# blink1mk2_v2d.net
KiCad netlist of a schematic drawn in EAGLE
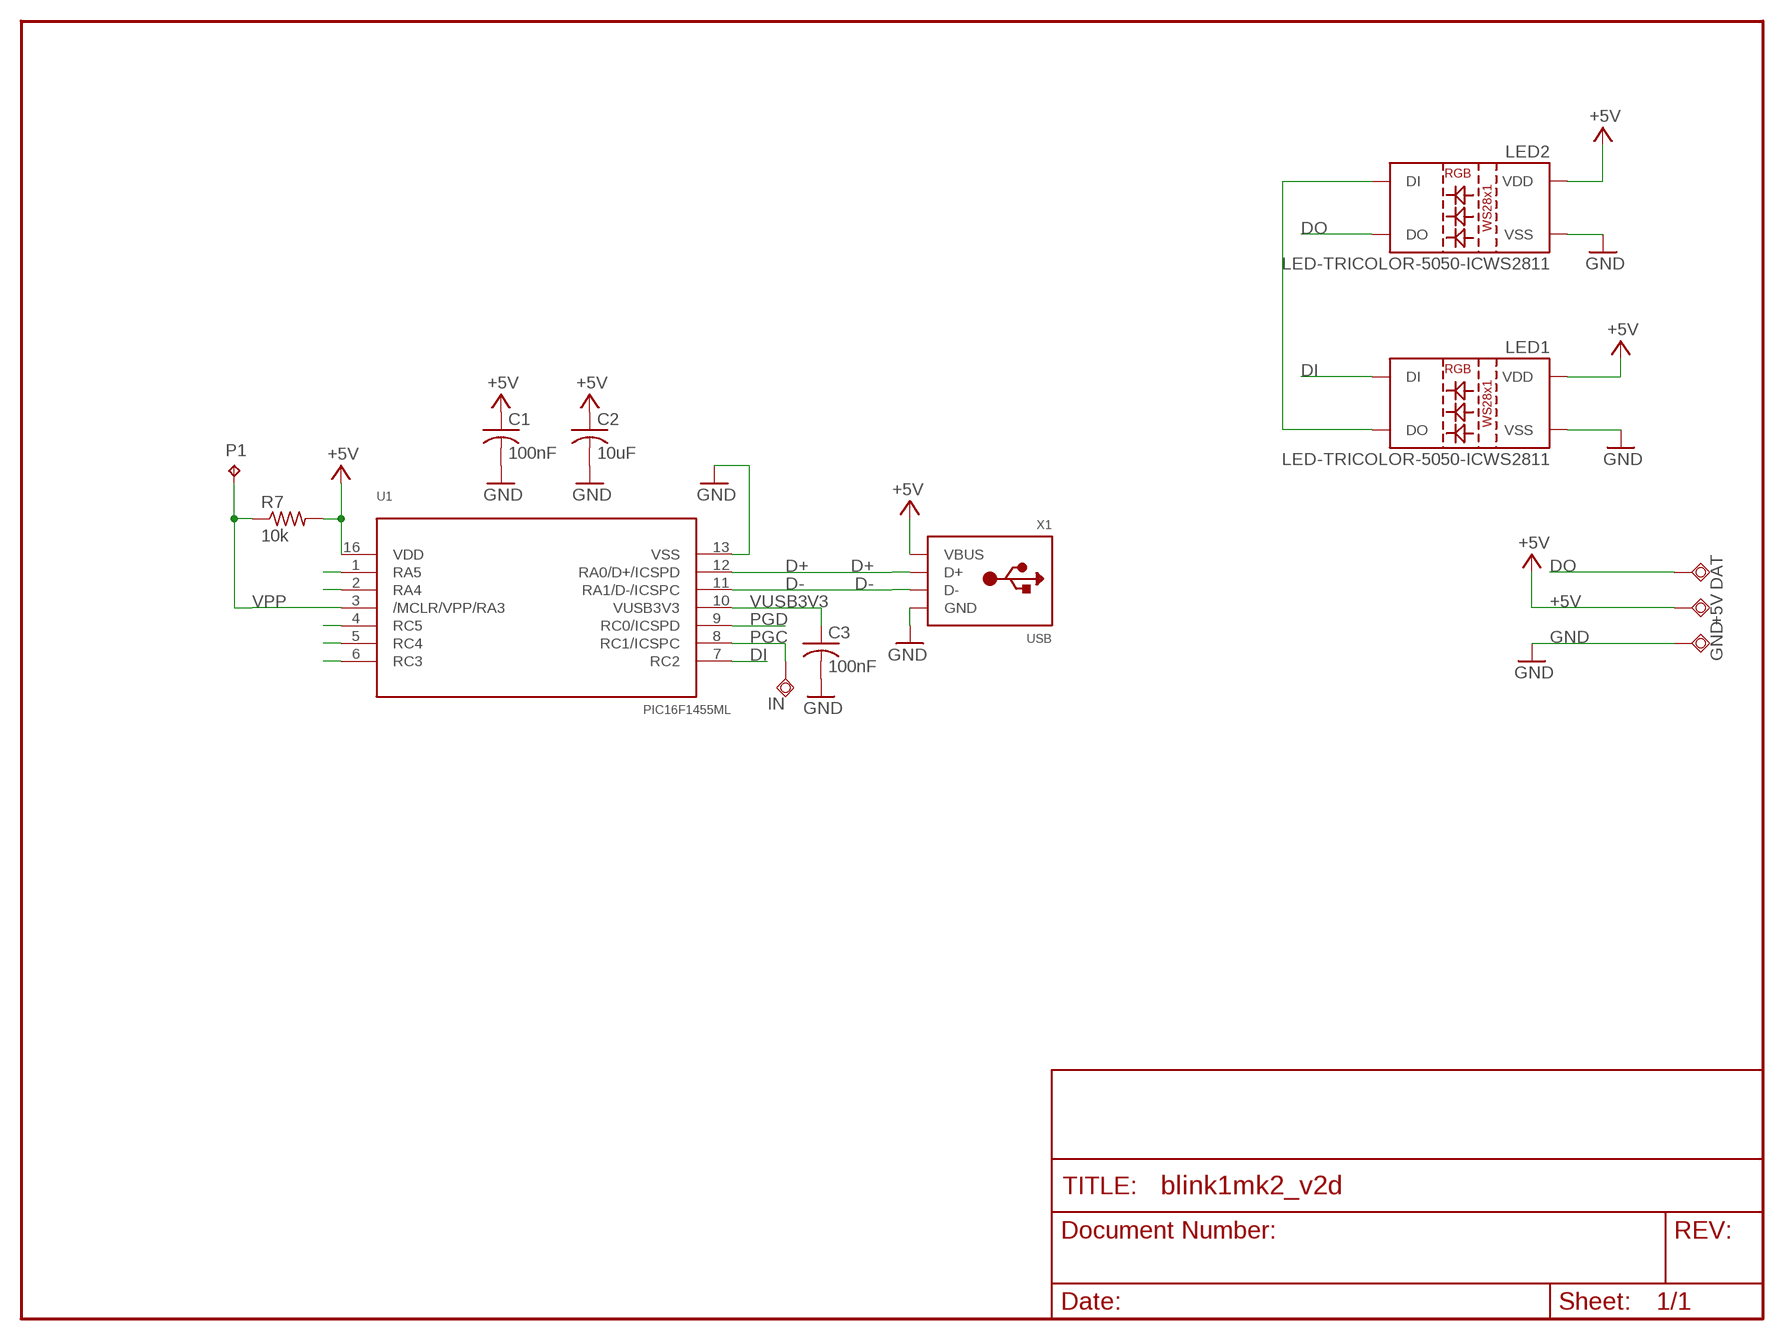
[diagram p0: schematic, sheet 1]

(export (version "E")
  (design (tool "Eeschema 10.0.6"))
  (components
    (comp (ref "+5V")
      (value "TPSQTP12SQ")
      (footprint "eagle-import:TP12SQ")
      (libsource (lib "eagle-import") (part "TPSQTP12SQ"))
    )
    (comp (ref "C1")
      (value "100nF")
      (footprint "eagle-import:C0603")
      (libsource (lib "eagle-import") (part "C-USC0603"))
    )
    (comp (ref "C2")
      (value "10uF")
      (footprint "eagle-import:C0603")
      (libsource (lib "eagle-import") (part "C-USC0603"))
    )
    (comp (ref "C3")
      (value "100nF")
      (footprint "eagle-import:C0603")
      (libsource (lib "eagle-import") (part "C-USC0603"))
    )
    (comp (ref "DAT")
      (value "TPSQTP12SQ")
      (footprint "eagle-import:TP12SQ")
      (libsource (lib "eagle-import") (part "TPSQTP12SQ"))
    )
    (comp (ref "GND")
      (value "TPSQTP12SQ")
      (footprint "eagle-import:TP12SQ")
      (libsource (lib "eagle-import") (part "TPSQTP12SQ"))
    )
    (comp (ref "IN")
      (value "TPSQTP12SQ")
      (footprint "eagle-import:TP12SQ")
      (libsource (lib "eagle-import") (part "TPSQTP12SQ"))
    )
    (comp (ref "LED1")
      (value "LED-TRICOLOR-5050-ICWS2811")
      (footprint "eagle-import:LED-TRICOLOR-5050-IC")
      (libsource (lib "eagle-import") (part "LED-TRICOLOR-5050-ICWS2811"))
    )
    (comp (ref "LED2")
      (value "LED-TRICOLOR-5050-ICWS2811")
      (footprint "eagle-import:LED-TRICOLOR-5050-IC")
      (libsource (lib "eagle-import") (part "LED-TRICOLOR-5050-ICWS2811"))
    )
    (comp (ref "P1")
      (value "TPTP11SQ")
      (footprint "eagle-import:TP11SQ")
      (libsource (lib "eagle-import") (part "TPTP11SQ"))
    )
    (comp (ref "R7")
      (value "10k")
      (footprint "eagle-import:R0603")
      (libsource (lib "eagle-import") (part "R-US_R0603"))
    )
    (comp (ref "U1")
      (value "PIC16F1455ML")
      (footprint "eagle-import:QFN16_4X4")
      (libsource (lib "eagle-import") (part "PIC16F1455ML"))
    )
    (comp (ref "X1")
      (value "USB")
      (footprint "eagle-import:MOLEX-48037-1000")
      (libsource (lib "eagle-import") (part "USB"))
    )
  )
  (nets
    (net (code "1") (name "+5V") (class "Default")
      (node (ref "+5V") (pin "TP") (pinfunction "TP_TP") (pintype "input"))
      (node (ref "C1") (pin "1") (pinfunction "1_1") (pintype "passive"))
      (node (ref "C2") (pin "1") (pinfunction "1_1") (pintype "passive"))
      (node (ref "LED1") (pin "3") (pinfunction "VDD_3") (pintype "bidirectional"))
      (node (ref "LED1") (pin "5") (pinfunction "VDD_5") (pintype "bidirectional"))
      (node (ref "LED2") (pin "3") (pinfunction "VDD_3") (pintype "bidirectional"))
      (node (ref "LED2") (pin "5") (pinfunction "VDD_5") (pintype "bidirectional"))
      (node (ref "R7") (pin "2") (pinfunction "2_2") (pintype "passive"))
      (node (ref "U1") (pin "16") (pinfunction "VDD_16") (pintype "bidirectional"))
      (node (ref "X1") (pin "1") (pinfunction "VBUS_1") (pintype "power_in"))
    )
    (net (code "2") (name "/D+") (class "Default")
      (node (ref "U1") (pin "12") (pinfunction "RA0/D+/ICSPD_12") (pintype "bidirectional"))
      (node (ref "X1") (pin "3") (pinfunction "D+_3") (pintype "bidirectional"))
    )
    (net (code "3") (name "/D-") (class "Default")
      (node (ref "U1") (pin "11") (pinfunction "RA1/D-/ICSPC_11") (pintype "bidirectional"))
      (node (ref "X1") (pin "2") (pinfunction "D-_2") (pintype "bidirectional"))
    )
    (net (code "4") (name "/DI") (class "Default")
      (node (ref "LED1") (pin "2") (pinfunction "DI_2") (pintype "bidirectional"))
      (node (ref "U1") (pin "7") (pinfunction "RC2_7") (pintype "bidirectional"))
    )
    (net (code "5") (name "/DO") (class "Default")
      (node (ref "DAT") (pin "TP") (pinfunction "TP_TP") (pintype "input"))
      (node (ref "LED2") (pin "1") (pinfunction "DO_1") (pintype "bidirectional"))
    )
    (net (code "6") (name "/PGC") (class "Default")
      (node (ref "IN") (pin "TP") (pinfunction "TP_TP") (pintype "input"))
      (node (ref "U1") (pin "8") (pinfunction "RC1/ICSPC_8") (pintype "bidirectional"))
    )
    (net (code "7") (name "/PGD") (class "Default")
      (node (ref "U1") (pin "9") (pinfunction "RC0/ICSPD_9") (pintype "bidirectional"))
    )
    (net (code "8") (name "/VPP") (class "Default")
      (node (ref "P1") (pin "TP") (pinfunction "TP_TP") (pintype "input"))
      (node (ref "R7") (pin "1") (pinfunction "1_1") (pintype "passive"))
      (node (ref "U1") (pin "3") (pinfunction "/MCLR/VPP/RA3_3") (pintype "bidirectional"))
    )
    (net (code "9") (name "/VUSB3V3") (class "Default")
      (node (ref "C3") (pin "1") (pinfunction "1_1") (pintype "passive"))
      (node (ref "U1") (pin "10") (pinfunction "VUSB3V3_10") (pintype "bidirectional"))
    )
    (net (code "10") (name "GND") (class "Default")
      (node (ref "C1") (pin "2") (pinfunction "2_2") (pintype "passive"))
      (node (ref "C2") (pin "2") (pinfunction "2_2") (pintype "passive"))
      (node (ref "C3") (pin "2") (pinfunction "2_2") (pintype "passive"))
      (node (ref "GND") (pin "TP") (pinfunction "TP_TP") (pintype "input"))
      (node (ref "LED1") (pin "6") (pinfunction "VSS_6") (pintype "bidirectional"))
      (node (ref "LED2") (pin "6") (pinfunction "VSS_6") (pintype "bidirectional"))
      (node (ref "U1") (pin "13") (pinfunction "VSS_13") (pintype "bidirectional"))
      (node (ref "X1") (pin "4") (pinfunction "GND_4") (pintype "power_in"))
    )
    (net (code "11") (name "Net-(LED1-DO)") (class "Default")
      (node (ref "LED1") (pin "1") (pinfunction "DO_1") (pintype "bidirectional"))
      (node (ref "LED2") (pin "2") (pinfunction "DI_2") (pintype "bidirectional"))
    )
    (net (code "12") (name "unconnected-(U1-RA4-Pad2)") (class "Default")
      (node (ref "U1") (pin "2") (pinfunction "RA4_2") (pintype "bidirectional"))
    )
    (net (code "13") (name "unconnected-(U1-RA5-Pad1)") (class "Default")
      (node (ref "U1") (pin "1") (pinfunction "RA5_1") (pintype "bidirectional"))
    )
    (net (code "14") (name "unconnected-(U1-RC3-Pad6)") (class "Default")
      (node (ref "U1") (pin "6") (pinfunction "RC3_6") (pintype "bidirectional"))
    )
    (net (code "15") (name "unconnected-(U1-RC4-Pad5)") (class "Default")
      (node (ref "U1") (pin "5") (pinfunction "RC4_5") (pintype "bidirectional"))
    )
    (net (code "16") (name "unconnected-(U1-RC5-Pad4)") (class "Default")
      (node (ref "U1") (pin "4") (pinfunction "RC5_4") (pintype "bidirectional"))
    )
  )
)
